# vusbtinyisp_smt_inline.net
KiCad netlist of a schematic drawn in EAGLE
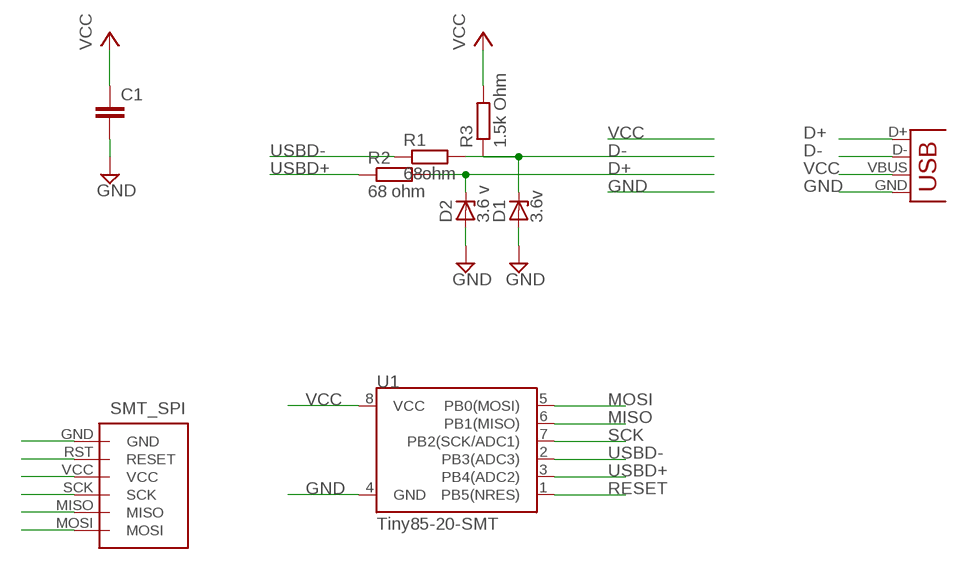
[diagram p0: schematic, sheet 1]

(export (version "E")
  (design (tool "Eeschema 10.0.6"))
  (components
    (comp (ref "C1")
      (value "CAP1206")
      (footprint "eagle-import:1206")
      (libsource (lib "eagle-import") (part "CAP1206"))
    )
    (comp (ref "D1")
      (value "3.6v")
      (footprint "eagle-import:SOT23")
      (libsource (lib "eagle-import") (part "ZENER-DIODESOT23"))
    )
    (comp (ref "D2")
      (value "3.6 v")
      (footprint "eagle-import:SOT23")
      (libsource (lib "eagle-import") (part "ZENER-DIODESOT23"))
    )
    (comp (ref "JP2")
      (value "USBSMD")
      (footprint "eagle-import:USB-MINIB")
      (libsource (lib "eagle-import") (part "USBSMD"))
    )
    (comp (ref "R1")
      (value "68ohm")
      (footprint "eagle-import:R0805")
      (libsource (lib "eagle-import") (part "R-EU_R0805"))
    )
    (comp (ref "R2")
      (value "68 ohm")
      (footprint "eagle-import:R0805")
      (libsource (lib "eagle-import") (part "R-EU_R0805"))
    )
    (comp (ref "R3")
      (value "1.5k Ohm")
      (footprint "eagle-import:R1206")
      (libsource (lib "eagle-import") (part "R-EU_R1206"))
    )
    (comp (ref "U$1")
      (value "SMT_ISP")
      (footprint "eagle-import:SMT_PADS")
      (libsource (lib "eagle-import") (part "SMT_ISP"))
    )
    (comp (ref "U1")
      (value "Tiny85-20-SMT")
      (footprint "eagle-import:SO08-EIAJ")
      (libsource (lib "eagle-import") (part "ATTINY45TINY85-20-SMT"))
    )
  )
  (nets
    (net (code "1") (name "/D+") (class "Default")
      (node (ref "D2") (pin "3") (pinfunction "C_3") (pintype "passive"))
      (node (ref "JP2") (pin "D+") (pinfunction "D+_D+") (pintype "bidirectional"))
      (node (ref "R2") (pin "2") (pinfunction "2_2") (pintype "passive"))
    )
    (net (code "2") (name "/D-") (class "Default")
      (node (ref "D1") (pin "3") (pinfunction "C_3") (pintype "passive"))
      (node (ref "JP2") (pin "D-") (pinfunction "D-_D-") (pintype "bidirectional"))
      (node (ref "R1") (pin "2") (pinfunction "2_2") (pintype "passive"))
      (node (ref "R3") (pin "1") (pinfunction "1_1") (pintype "passive"))
    )
    (net (code "3") (name "/MISO") (class "Default")
      (node (ref "U$1") (pin "MISO") (pinfunction "MISO_MISO") (pintype "bidirectional"))
      (node (ref "U1") (pin "6") (pinfunction "PB1(MISO)_6") (pintype "bidirectional"))
    )
    (net (code "4") (name "/MOSI") (class "Default")
      (node (ref "U$1") (pin "MOSI") (pinfunction "MOSI_MOSI") (pintype "bidirectional"))
      (node (ref "U1") (pin "5") (pinfunction "PB0(MOSI)_5") (pintype "bidirectional"))
    )
    (net (code "5") (name "/RESET") (class "Default")
      (node (ref "U$1") (pin "RST") (pinfunction "RESET_RST") (pintype "bidirectional"))
      (node (ref "U1") (pin "1") (pinfunction "PB5(NRES)_1") (pintype "bidirectional"))
    )
    (net (code "6") (name "/SCK") (class "Default")
      (node (ref "U$1") (pin "SCK") (pinfunction "SCK_SCK") (pintype "bidirectional"))
      (node (ref "U1") (pin "7") (pinfunction "PB2(SCK/ADC1)_7") (pintype "bidirectional"))
    )
    (net (code "7") (name "/USBD+") (class "Default")
      (node (ref "R2") (pin "1") (pinfunction "1_1") (pintype "passive"))
      (node (ref "U1") (pin "3") (pinfunction "PB4(ADC2)_3") (pintype "bidirectional"))
    )
    (net (code "8") (name "/USBD-") (class "Default")
      (node (ref "R1") (pin "1") (pinfunction "1_1") (pintype "passive"))
      (node (ref "U1") (pin "2") (pinfunction "PB3(ADC3)_2") (pintype "bidirectional"))
    )
    (net (code "9") (name "GND") (class "Default")
      (node (ref "C1") (pin "2") (pinfunction "2_2") (pintype "passive"))
      (node (ref "D1") (pin "1") (pinfunction "A_1") (pintype "passive"))
      (node (ref "D2") (pin "1") (pinfunction "A_1") (pintype "passive"))
      (node (ref "JP2") (pin "GND") (pinfunction "GND_GND") (pintype "bidirectional"))
      (node (ref "U$1") (pin "GND") (pinfunction "GND_GND") (pintype "bidirectional"))
      (node (ref "U1") (pin "4") (pinfunction "GND_4") (pintype "bidirectional"))
    )
    (net (code "10") (name "VCC") (class "Default")
      (node (ref "C1") (pin "1") (pinfunction "1_1") (pintype "passive"))
      (node (ref "JP2") (pin "VBUS") (pinfunction "VBUS_VBUS") (pintype "bidirectional"))
      (node (ref "R3") (pin "2") (pinfunction "2_2") (pintype "passive"))
      (node (ref "U$1") (pin "VCC") (pinfunction "VCC_VCC") (pintype "bidirectional"))
      (node (ref "U1") (pin "8") (pinfunction "VCC_8") (pintype "bidirectional"))
    )
  )
)
